# airflow_sensor_teensy2.net
KiCad netlist of a schematic drawn in EAGLE
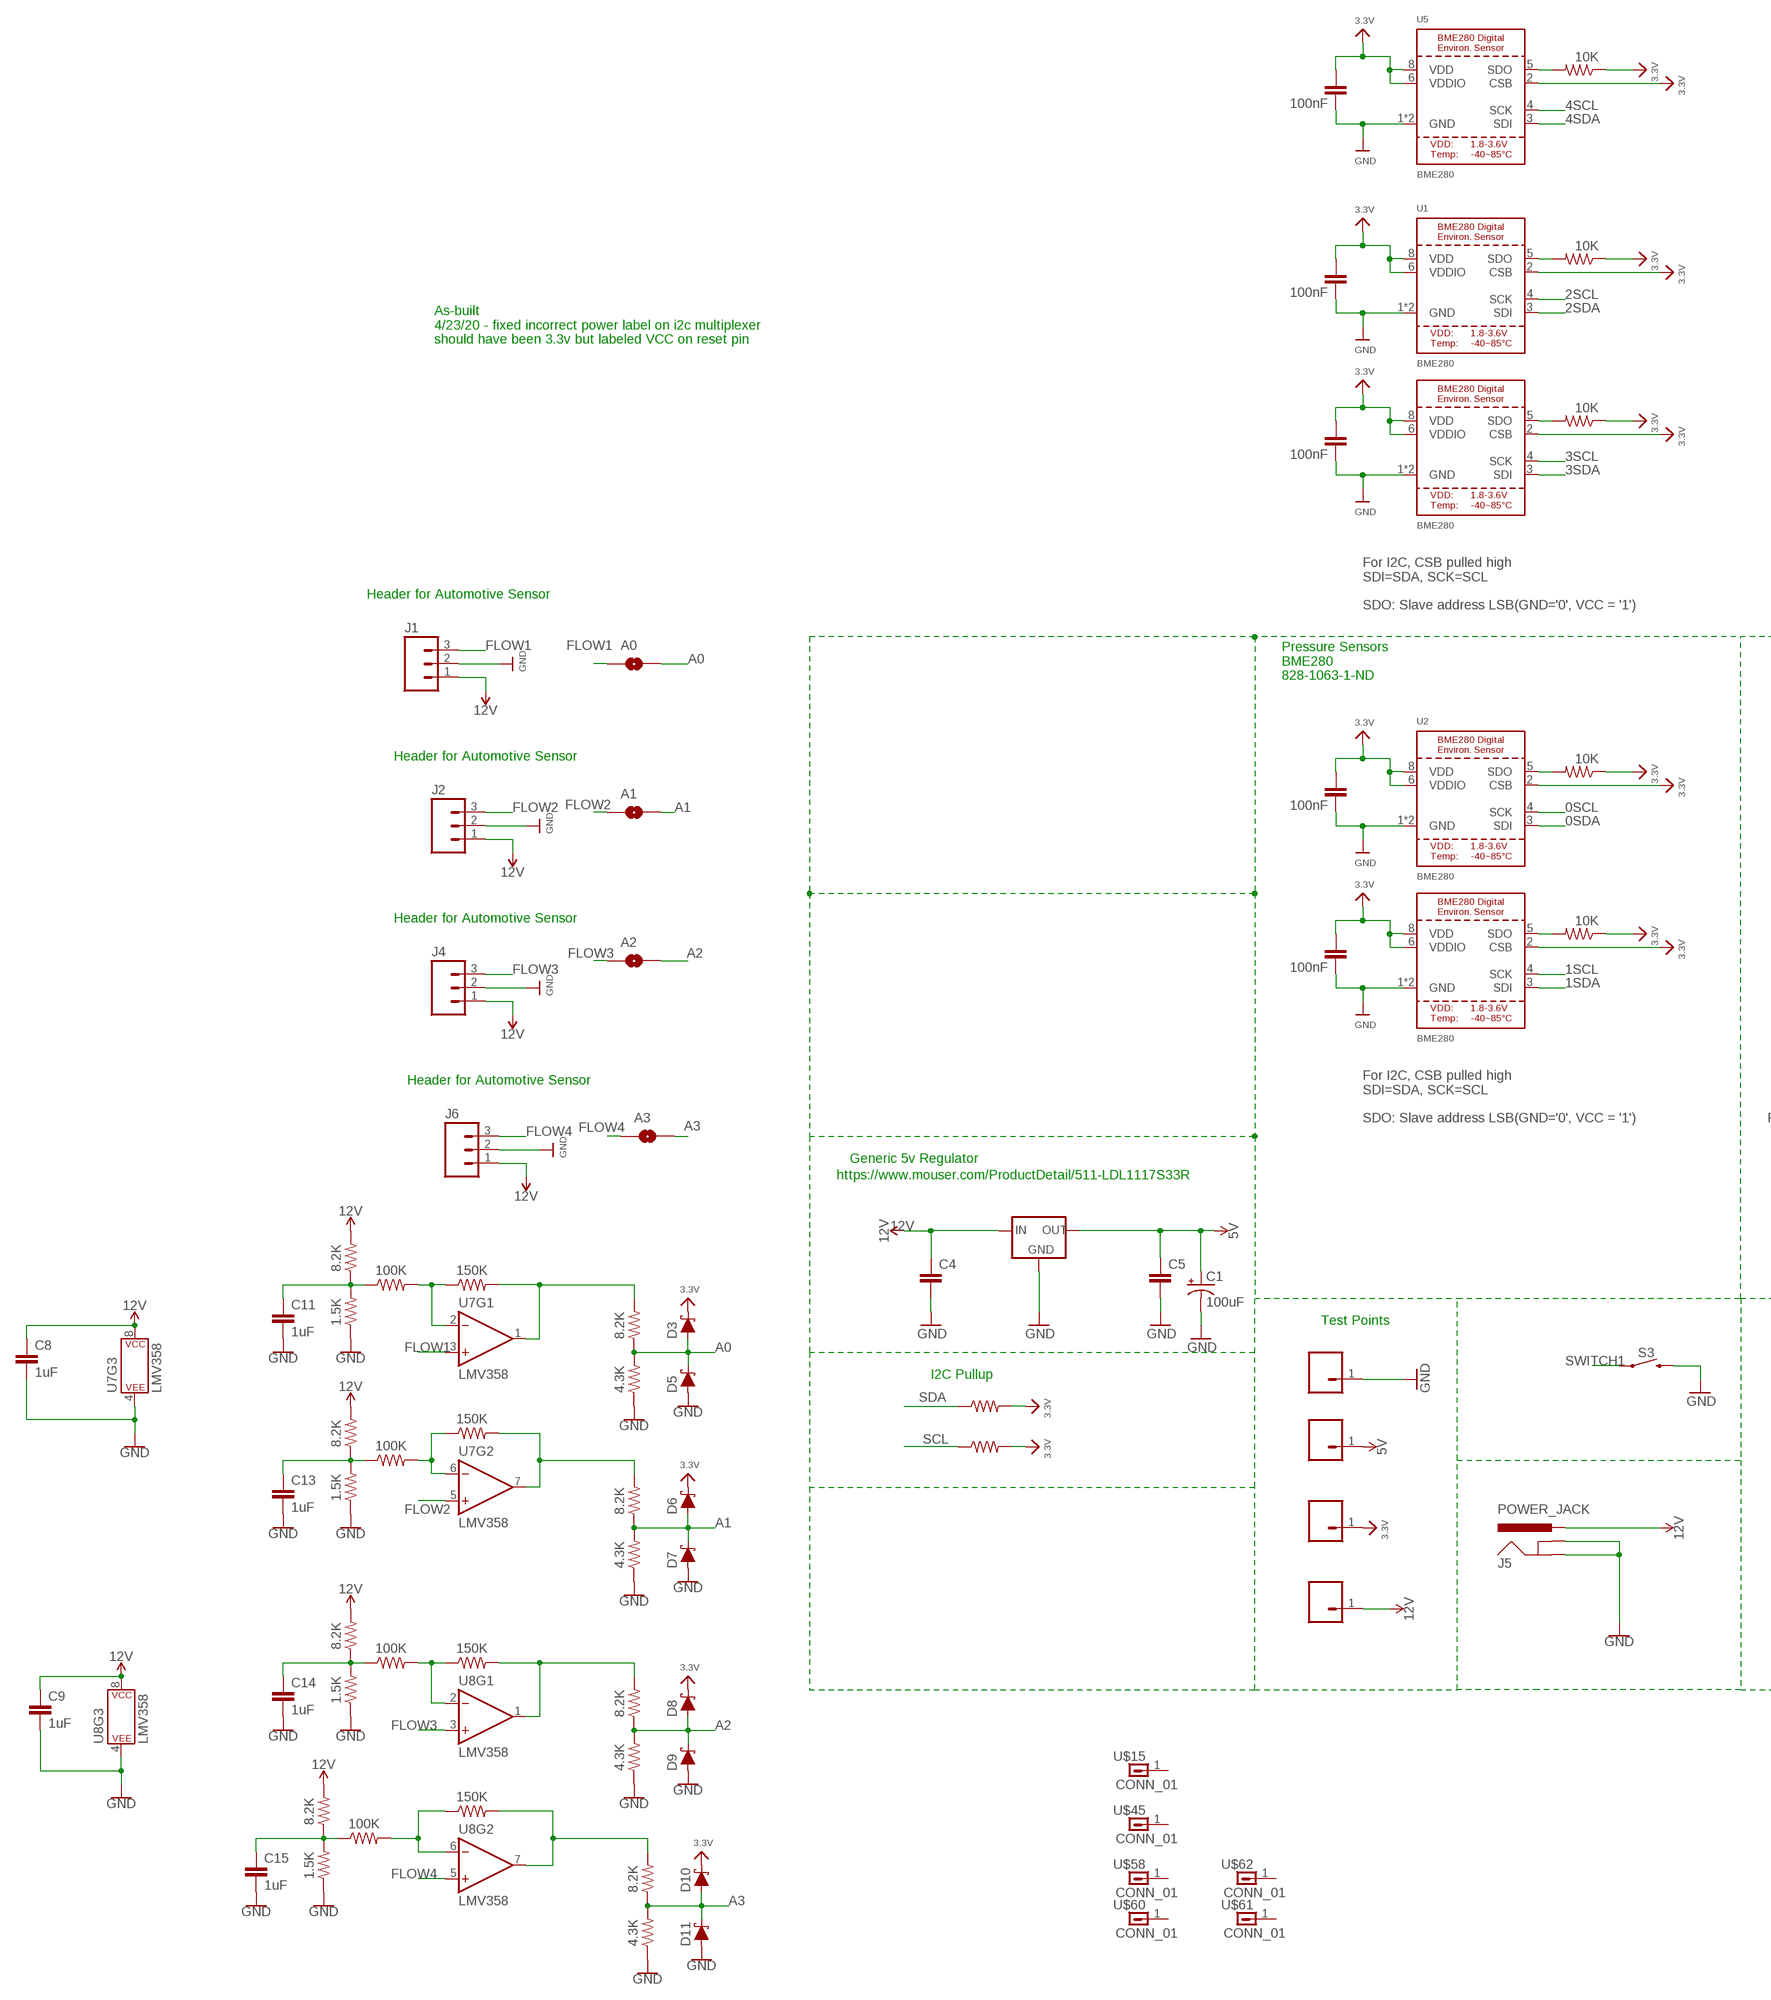
[diagram p0: schematic, sheet 1, part 1 of 2]
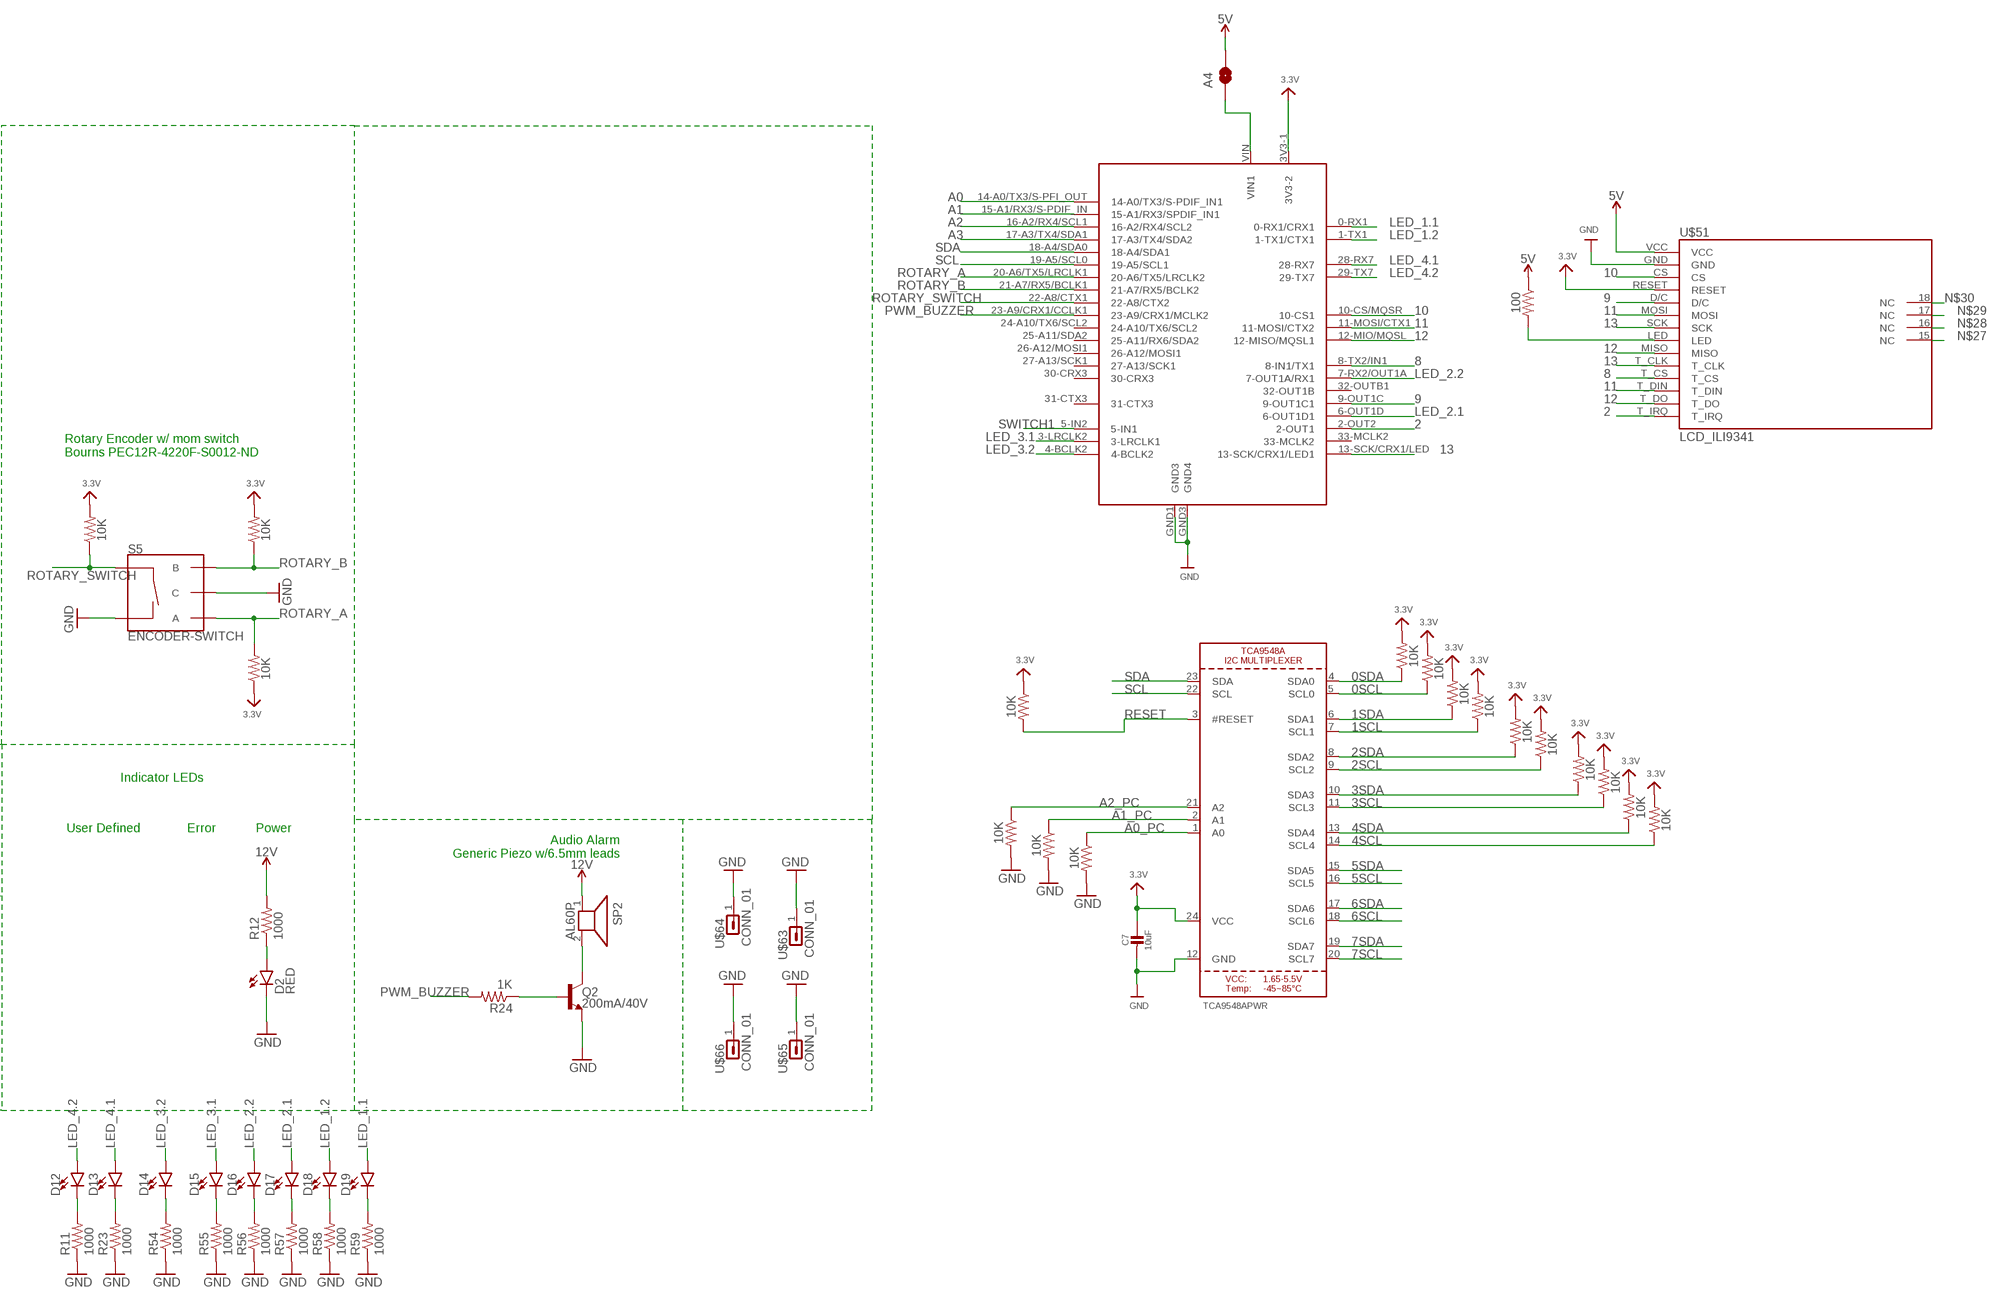
[diagram p1: schematic, sheet 1, part 2 of 2]

(export (version "E")
  (design (tool "Eeschema 10.0.6"))
  (components
    (comp (ref "3V_REGULATOR")
      (value "LDL1117_5V_REG")
      (footprint "eagle-import:SOT223")
      (libsource (lib "eagle-import") (part "LDL1117_5V_REG"))
    )
    (comp (ref "A0")
      (value "JUMPER-SMT_2_NO_NO-SILK")
      (footprint "eagle-import:SMT-JUMPER_2_NO_NO-SILK")
      (libsource (lib "eagle-import") (part "JUMPER-SMT_2_NO_NO-SILK"))
    )
    (comp (ref "A1")
      (value "JUMPER-SMT_2_NO_NO-SILK")
      (footprint "eagle-import:SMT-JUMPER_2_NO_NO-SILK")
      (libsource (lib "eagle-import") (part "JUMPER-SMT_2_NO_NO-SILK"))
    )
    (comp (ref "A2")
      (value "JUMPER-SMT_2_NO_NO-SILK")
      (footprint "eagle-import:SMT-JUMPER_2_NO_NO-SILK")
      (libsource (lib "eagle-import") (part "JUMPER-SMT_2_NO_NO-SILK"))
    )
    (comp (ref "A3")
      (value "JUMPER-SMT_2_NO_NO-SILK")
      (footprint "eagle-import:SMT-JUMPER_2_NO_NO-SILK")
      (libsource (lib "eagle-import") (part "JUMPER-SMT_2_NO_NO-SILK"))
    )
    (comp (ref "A4")
      (value "JUMPER-SMT_2_NO_NO-SILK")
      (footprint "eagle-import:SMT-JUMPER_2_NO_NO-SILK")
      (libsource (lib "eagle-import") (part "JUMPER-SMT_2_NO_NO-SILK"))
    )
    (comp (ref "C1")
      (value "100uF")
      (footprint "eagle-import:CPOL-RADIAL-2.5MM-6.5MM")
      (libsource (lib "eagle-import") (part "100UF-POLAR-RADIAL-2.5MM-25V-20%"))
    )
    (comp (ref "C2")
      (value "100nF")
      (footprint "eagle-import:0805")
      (libsource (lib "eagle-import") (part "CAP-0805"))
    )
    (comp (ref "C3")
      (value "100nF")
      (footprint "eagle-import:0805")
      (libsource (lib "eagle-import") (part "CAP-0805"))
    )
    (comp (ref "C4")
      (value "CAP-0805")
      (footprint "eagle-import:0805")
      (libsource (lib "eagle-import") (part "CAP-0805"))
    )
    (comp (ref "C5")
      (value "CAP-0805")
      (footprint "eagle-import:0805")
      (libsource (lib "eagle-import") (part "CAP-0805"))
    )
    (comp (ref "C6")
      (value "100nF")
      (footprint "eagle-import:0805")
      (libsource (lib "eagle-import") (part "CAP-0805"))
    )
    (comp (ref "C7")
      (value "10uF")
      (footprint "eagle-import:0805-NO")
      (libsource (lib "eagle-import") (part "CAP_CERAMIC0805-NOOUTLINE"))
    )
    (comp (ref "C8")
      (value "1uF")
      (footprint "eagle-import:0805")
      (libsource (lib "eagle-import") (part "CAP-0805"))
    )
    (comp (ref "C9")
      (value "1uF")
      (footprint "eagle-import:0805")
      (libsource (lib "eagle-import") (part "CAP-0805"))
    )
    (comp (ref "C10")
      (value "100nF")
      (footprint "eagle-import:0805")
      (libsource (lib "eagle-import") (part "CAP-0805"))
    )
    (comp (ref "C11")
      (value "1uF")
      (footprint "eagle-import:0805")
      (libsource (lib "eagle-import") (part "CAP-0805"))
    )
    (comp (ref "C12")
      (value "100nF")
      (footprint "eagle-import:0805")
      (libsource (lib "eagle-import") (part "CAP-0805"))
    )
    (comp (ref "C13")
      (value "1uF")
      (footprint "eagle-import:0805")
      (libsource (lib "eagle-import") (part "CAP-0805"))
    )
    (comp (ref "C14")
      (value "1uF")
      (footprint "eagle-import:0805")
      (libsource (lib "eagle-import") (part "CAP-0805"))
    )
    (comp (ref "C15")
      (value "1uF")
      (footprint "eagle-import:0805")
      (libsource (lib "eagle-import") (part "CAP-0805"))
    )
    (comp (ref "D2")
      (value "RED")
      (footprint "eagle-import:LED-1206")
      (libsource (lib "eagle-import") (part "LED-RED1206"))
    )
    (comp (ref "D3")
      (value "3A/40V/500mV")
      (footprint "eagle-import:SMA-DIODE")
      (libsource (lib "eagle-import") (part "DIODE-SCHOTTKY-B340A"))
    )
    (comp (ref "D5")
      (value "3A/40V/500mV")
      (footprint "eagle-import:SMA-DIODE")
      (libsource (lib "eagle-import") (part "DIODE-SCHOTTKY-B340A"))
    )
    (comp (ref "D6")
      (value "3A/40V/500mV")
      (footprint "eagle-import:SMA-DIODE")
      (libsource (lib "eagle-import") (part "DIODE-SCHOTTKY-B340A"))
    )
    (comp (ref "D7")
      (value "3A/40V/500mV")
      (footprint "eagle-import:SMA-DIODE")
      (libsource (lib "eagle-import") (part "DIODE-SCHOTTKY-B340A"))
    )
    (comp (ref "D8")
      (value "3A/40V/500mV")
      (footprint "eagle-import:SMA-DIODE")
      (libsource (lib "eagle-import") (part "DIODE-SCHOTTKY-B340A"))
    )
    (comp (ref "D9")
      (value "3A/40V/500mV")
      (footprint "eagle-import:SMA-DIODE")
      (libsource (lib "eagle-import") (part "DIODE-SCHOTTKY-B340A"))
    )
    (comp (ref "D10")
      (value "3A/40V/500mV")
      (footprint "eagle-import:SMA-DIODE")
      (libsource (lib "eagle-import") (part "DIODE-SCHOTTKY-B340A"))
    )
    (comp (ref "D11")
      (value "3A/40V/500mV")
      (footprint "eagle-import:SMA-DIODE")
      (libsource (lib "eagle-import") (part "DIODE-SCHOTTKY-B340A"))
    )
    (comp (ref "D12")
      (value "LED5MM")
      (footprint "eagle-import:LED_5MM")
      (libsource (lib "eagle-import") (part "LED5MM"))
    )
    (comp (ref "D13")
      (value "LED5MM")
      (footprint "eagle-import:LED_5MM")
      (libsource (lib "eagle-import") (part "LED5MM"))
    )
    (comp (ref "D14")
      (value "LED5MM")
      (footprint "eagle-import:LED_5MM")
      (libsource (lib "eagle-import") (part "LED5MM"))
    )
    (comp (ref "D15")
      (value "LED5MM")
      (footprint "eagle-import:LED_5MM")
      (libsource (lib "eagle-import") (part "LED5MM"))
    )
    (comp (ref "D16")
      (value "LED5MM")
      (footprint "eagle-import:LED_5MM")
      (libsource (lib "eagle-import") (part "LED5MM"))
    )
    (comp (ref "D17")
      (value "LED5MM")
      (footprint "eagle-import:LED_5MM")
      (libsource (lib "eagle-import") (part "LED5MM"))
    )
    (comp (ref "D18")
      (value "LED5MM")
      (footprint "eagle-import:LED_5MM")
      (libsource (lib "eagle-import") (part "LED5MM"))
    )
    (comp (ref "D19")
      (value "LED5MM")
      (footprint "eagle-import:LED_5MM")
      (libsource (lib "eagle-import") (part "LED5MM"))
    )
    (comp (ref "J1")
      (value "M03SCREW")
      (footprint "eagle-import:SCREWTERMINAL-3.5MM-3")
      (libsource (lib "eagle-import") (part "M03SCREW"))
    )
    (comp (ref "J2")
      (value "M03SCREW")
      (footprint "eagle-import:SCREWTERMINAL-3.5MM-3")
      (libsource (lib "eagle-import") (part "M03SCREW"))
    )
    (comp (ref "J4")
      (value "M03SCREW")
      (footprint "eagle-import:SCREWTERMINAL-3.5MM-3")
      (libsource (lib "eagle-import") (part "M03SCREW"))
    )
    (comp (ref "J5")
      (value "POWER_JACK")
      (footprint "eagle-import:POWER_JACK_PTH")
      (libsource (lib "eagle-import") (part "POWER_JACK"))
    )
    (comp (ref "J6")
      (value "M03SCREW")
      (footprint "eagle-import:SCREWTERMINAL-3.5MM-3")
      (libsource (lib "eagle-import") (part "M03SCREW"))
    )
    (comp (ref "Q2")
      (value "200mA/40V")
      (footprint "eagle-import:TO-92")
      (libsource (lib "eagle-import") (part "TRANS_NPN-2N3904"))
    )
    (comp (ref "R1")
      (value "10K")
      (footprint "eagle-import:0805")
      (libsource (lib "eagle-import") (part "RESISTOR0805-RES"))
    )
    (comp (ref "R2")
      (value "10K")
      (footprint "eagle-import:0805")
      (libsource (lib "eagle-import") (part "RESISTOR0805-RES"))
    )
    (comp (ref "R3")
      (value "10K")
      (footprint "eagle-import:0805")
      (libsource (lib "eagle-import") (part "RESISTOR0805-RES"))
    )
    (comp (ref "R4")
      (value "10K")
      (footprint "eagle-import:0805")
      (libsource (lib "eagle-import") (part "RESISTOR0805-RES"))
    )
    (comp (ref "R5")
      (value "10K")
      (footprint "eagle-import:0805")
      (libsource (lib "eagle-import") (part "RESISTOR0805-RES"))
    )
    (comp (ref "R6")
      (value "10K")
      (footprint "eagle-import:0805")
      (libsource (lib "eagle-import") (part "0.3OHM-0805-1/8W-1%"))
    )
    (comp (ref "R7")
      (value "10K")
      (footprint "eagle-import:0805")
      (libsource (lib "eagle-import") (part "0.3OHM-0805-1/8W-1%"))
    )
    (comp (ref "R8")
      (value "10K")
      (footprint "eagle-import:0805")
      (libsource (lib "eagle-import") (part "0.3OHM-0805-1/8W-1%"))
    )
    (comp (ref "R9")
      (value "10K")
      (footprint "eagle-import:0805")
      (libsource (lib "eagle-import") (part "0.3OHM-0805-1/8W-1%"))
    )
    (comp (ref "R10")
      (value "10K")
      (footprint "eagle-import:0805")
      (libsource (lib "eagle-import") (part "0.3OHM-0805-1/8W-1%"))
    )
    (comp (ref "R11")
      (value "1000")
      (footprint "eagle-import:0805")
      (libsource (lib "eagle-import") (part "RESISTOR0805-RES"))
    )
    (comp (ref "R12")
      (value "1000")
      (footprint "eagle-import:0805")
      (libsource (lib "eagle-import") (part "RESISTOR0805-RES"))
    )
    (comp (ref "R13")
      (value "10K")
      (footprint "eagle-import:0805")
      (libsource (lib "eagle-import") (part "0.3OHM-0805-1/8W-1%"))
    )
    (comp (ref "R14")
      (value "10K")
      (footprint "eagle-import:0805")
      (libsource (lib "eagle-import") (part "0.3OHM-0805-1/8W-1%"))
    )
    (comp (ref "R15")
      (value "10K")
      (footprint "eagle-import:0805")
      (libsource (lib "eagle-import") (part "0.3OHM-0805-1/8W-1%"))
    )
    (comp (ref "R16")
      (value "10K")
      (footprint "eagle-import:0805")
      (libsource (lib "eagle-import") (part "0.3OHM-0805-1/8W-1%"))
    )
    (comp (ref "R17")
      (value "10K")
      (footprint "eagle-import:0805")
      (libsource (lib "eagle-import") (part "0.3OHM-0805-1/8W-1%"))
    )
    (comp (ref "R18")
      (value "10K")
      (footprint "eagle-import:0805")
      (libsource (lib "eagle-import") (part "0.3OHM-0805-1/8W-1%"))
    )
    (comp (ref "R19")
      (value "10K")
      (footprint "eagle-import:0805")
      (libsource (lib "eagle-import") (part "0.3OHM-0805-1/8W-1%"))
    )
    (comp (ref "R20")
      (value "10K")
      (footprint "eagle-import:0805")
      (libsource (lib "eagle-import") (part "0.3OHM-0805-1/8W-1%"))
    )
    (comp (ref "R21")
      (value "0.3")
      (footprint "eagle-import:0805")
      (libsource (lib "eagle-import") (part "0.3OHM-0805-1/8W-1%"))
    )
    (comp (ref "R22")
      (value "0.3")
      (footprint "eagle-import:0805")
      (libsource (lib "eagle-import") (part "0.3OHM-0805-1/8W-1%"))
    )
    (comp (ref "R23")
      (value "1000")
      (footprint "eagle-import:0805")
      (libsource (lib "eagle-import") (part "RESISTOR0805-RES"))
    )
    (comp (ref "R24")
      (value "1K")
      (footprint "eagle-import:0805")
      (libsource (lib "eagle-import") (part "RESISTOR0805-RES"))
    )
    (comp (ref "R25")
      (value "10K")
      (footprint "eagle-import:0805")
      (libsource (lib "eagle-import") (part "0.3OHM-0805-1/8W-1%"))
    )
    (comp (ref "R26")
      (value "10K")
      (footprint "eagle-import:0805")
      (libsource (lib "eagle-import") (part "0.3OHM-0805-1/8W-1%"))
    )
    (comp (ref "R27")
      (value "10K")
      (footprint "eagle-import:0805")
      (libsource (lib "eagle-import") (part "0.3OHM-0805-1/8W-1%"))
    )
    (comp (ref "R28")
      (value "10K")
      (footprint "eagle-import:0805")
      (libsource (lib "eagle-import") (part "0.3OHM-0805-1/8W-1%"))
    )
    (comp (ref "R29")
      (value "150K")
      (footprint "eagle-import:0805")
      (libsource (lib "eagle-import") (part "0.3OHM-0805-1/8W-1%"))
    )
    (comp (ref "R30")
      (value "150K")
      (footprint "eagle-import:0805")
      (libsource (lib "eagle-import") (part "0.3OHM-0805-1/8W-1%"))
    )
    (comp (ref "R31")
      (value "150K")
      (footprint "eagle-import:0805")
      (libsource (lib "eagle-import") (part "0.3OHM-0805-1/8W-1%"))
    )
    (comp (ref "R32")
      (value "150K")
      (footprint "eagle-import:0805")
      (libsource (lib "eagle-import") (part "0.3OHM-0805-1/8W-1%"))
    )
    (comp (ref "R33")
      (value "4.3K")
      (footprint "eagle-import:0805")
      (libsource (lib "eagle-import") (part "0.3OHM-0805-1/8W-1%"))
    )
    (comp (ref "R34")
      (value "8.2K")
      (footprint "eagle-import:0805")
      (libsource (lib "eagle-import") (part "0.3OHM-0805-1/8W-1%"))
    )
    (comp (ref "R35")
      (value "4.3K")
      (footprint "eagle-import:0805")
      (libsource (lib "eagle-import") (part "0.3OHM-0805-1/8W-1%"))
    )
    (comp (ref "R36")
      (value "8.2K")
      (footprint "eagle-import:0805")
      (libsource (lib "eagle-import") (part "0.3OHM-0805-1/8W-1%"))
    )
    (comp (ref "R37")
      (value "4.3K")
      (footprint "eagle-import:0805")
      (libsource (lib "eagle-import") (part "0.3OHM-0805-1/8W-1%"))
    )
    (comp (ref "R38")
      (value "8.2K")
      (footprint "eagle-import:0805")
      (libsource (lib "eagle-import") (part "0.3OHM-0805-1/8W-1%"))
    )
    (comp (ref "R39")
      (value "4.3K")
      (footprint "eagle-import:0805")
      (libsource (lib "eagle-import") (part "0.3OHM-0805-1/8W-1%"))
    )
    (comp (ref "R40")
      (value "8.2K")
      (footprint "eagle-import:0805")
      (libsource (lib "eagle-import") (part "0.3OHM-0805-1/8W-1%"))
    )
    (comp (ref "R41")
      (value "8.2K")
      (footprint "eagle-import:0805")
      (libsource (lib "eagle-import") (part "0.3OHM-0805-1/8W-1%"))
    )
    (comp (ref "R42")
      (value "1.5K")
      (footprint "eagle-import:0805")
      (libsource (lib "eagle-import") (part "0.3OHM-0805-1/8W-1%"))
    )
    (comp (ref "R43")
      (value "100K")
      (footprint "eagle-import:0805")
      (libsource (lib "eagle-import") (part "0.3OHM-0805-1/8W-1%"))
    )
    (comp (ref "R44")
      (value "8.2K")
      (footprint "eagle-import:0805")
      (libsource (lib "eagle-import") (part "0.3OHM-0805-1/8W-1%"))
    )
    (comp (ref "R45")
      (value "1.5K")
      (footprint "eagle-import:0805")
      (libsource (lib "eagle-import") (part "0.3OHM-0805-1/8W-1%"))
    )
    (comp (ref "R46")
      (value "100K")
      (footprint "eagle-import:0805")
      (libsource (lib "eagle-import") (part "0.3OHM-0805-1/8W-1%"))
    )
    (comp (ref "R47")
      (value "8.2K")
      (footprint "eagle-import:0805")
      (libsource (lib "eagle-import") (part "0.3OHM-0805-1/8W-1%"))
    )
    (comp (ref "R48")
      (value "1.5K")
      (footprint "eagle-import:0805")
      (libsource (lib "eagle-import") (part "0.3OHM-0805-1/8W-1%"))
    )
    (comp (ref "R49")
      (value "100K")
      (footprint "eagle-import:0805")
      (libsource (lib "eagle-import") (part "0.3OHM-0805-1/8W-1%"))
    )
    (comp (ref "R50")
      (value "8.2K")
      (footprint "eagle-import:0805")
      (libsource (lib "eagle-import") (part "0.3OHM-0805-1/8W-1%"))
    )
    (comp (ref "R51")
      (value "1.5K")
      (footprint "eagle-import:0805")
      (libsource (lib "eagle-import") (part "0.3OHM-0805-1/8W-1%"))
    )
    (comp (ref "R52")
      (value "100K")
      (footprint "eagle-import:0805")
      (libsource (lib "eagle-import") (part "0.3OHM-0805-1/8W-1%"))
    )
    (comp (ref "R53")
      (value "100")
      (footprint "eagle-import:0805")
      (libsource (lib "eagle-import") (part "0.3OHM-0805-1/8W-1%"))
    )
    (comp (ref "R54")
      (value "1000")
      (footprint "eagle-import:0805")
      (libsource (lib "eagle-import") (part "RESISTOR0805-RES"))
    )
    (comp (ref "R55")
      (value "1000")
      (footprint "eagle-import:0805")
      (libsource (lib "eagle-import") (part "RESISTOR0805-RES"))
    )
    (comp (ref "R56")
      (value "1000")
      (footprint "eagle-import:0805")
      (libsource (lib "eagle-import") (part "RESISTOR0805-RES"))
    )
    (comp (ref "R57")
      (value "1000")
      (footprint "eagle-import:0805")
      (libsource (lib "eagle-import") (part "RESISTOR0805-RES"))
    )
    (comp (ref "R58")
      (value "1000")
      (footprint "eagle-import:0805")
      (libsource (lib "eagle-import") (part "RESISTOR0805-RES"))
    )
    (comp (ref "R59")
      (value "1000")
      (footprint "eagle-import:0805")
      (libsource (lib "eagle-import") (part "RESISTOR0805-RES"))
    )
    (comp (ref "S3")
      (value "MOMENTARY-SWITCH-SPST-PTH-6.0MM-KIT")
      (footprint "eagle-import:TACTILE_SWITCH_PTH_6.0MM_KIT")
      (libsource (lib "eagle-import") (part "MOMENTARY-SWITCH-SPST-PTH-6.0MM-KIT"))
    )
    (comp (ref "S5")
      (value "ENCODER-SWITCH")
      (footprint "eagle-import:ROTARY_ENC_PLAIN")
      (libsource (lib "eagle-import") (part "ENCODER-SWITCH"))
    )
    (comp (ref "SP2")
      (value "AL60P")
      (footprint "eagle-import:AL60P")
      (libsource (lib "eagle-import") (part "AL60P"))
    )
    (comp (ref "U$15")
      (value "CONN_01")
      (footprint "eagle-import:1X01-#6_MACHINE")
      (libsource (lib "eagle-import") (part "CONN_01"))
    )
    (comp (ref "U$20")
      (value "CONN_0138MILL")
      (footprint "eagle-import:1X01-40MILL")
      (libsource (lib "eagle-import") (part "th_libraries3_CONN_0138MILL"))
    )
    (comp (ref "U$31")
      (value "CONN_0138MILL")
      (footprint "eagle-import:1X01-40MILL")
      (libsource (lib "eagle-import") (part "th_libraries3_CONN_0138MILL"))
    )
    (comp (ref "U$40")
      (value "CONN_0138MILL")
      (footprint "eagle-import:1X01-40MILL")
      (libsource (lib "eagle-import") (part "th_libraries3_CONN_0138MILL"))
    )
    (comp (ref "U$45")
      (value "CONN_01")
      (footprint "eagle-import:1X01-#6_MACHINE")
      (libsource (lib "eagle-import") (part "CONN_01"))
    )
    (comp (ref "U$51")
      (value "LCD_ILI9341")
      (footprint "eagle-import:ILI9341")
      (libsource (lib "eagle-import") (part "LCD_ILI9341"))
    )
    (comp (ref "U$58")
      (value "CONN_01")
      (footprint "eagle-import:1X01-#6_MACHINE")
      (libsource (lib "eagle-import") (part "CONN_01"))
    )
    (comp (ref "U$59")
      (value "CONN_0138MILL")
      (footprint "eagle-import:1X01-40MILL")
      (libsource (lib "eagle-import") (part "th_libraries3_CONN_0138MILL"))
    )
    (comp (ref "U$60")
      (value "CONN_01")
      (footprint "eagle-import:1X01-#6_MACHINE")
      (libsource (lib "eagle-import") (part "CONN_01"))
    )
    (comp (ref "U$61")
      (value "CONN_01")
      (footprint "eagle-import:1X01-#6_MACHINE")
      (libsource (lib "eagle-import") (part "CONN_01"))
    )
    (comp (ref "U$62")
      (value "CONN_01")
      (footprint "eagle-import:1X01-#6_MACHINE")
      (libsource (lib "eagle-import") (part "CONN_01"))
    )
    (comp (ref "U$63")
      (value "CONN_01")
      (footprint "eagle-import:1X01-#6_MACHINE")
      (libsource (lib "eagle-import") (part "CONN_01"))
    )
    (comp (ref "U$64")
      (value "CONN_01")
      (footprint "eagle-import:1X01-#6_MACHINE")
      (libsource (lib "eagle-import") (part "CONN_01"))
    )
    (comp (ref "U$65")
      (value "CONN_01")
      (footprint "eagle-import:1X01-#6_MACHINE")
      (libsource (lib "eagle-import") (part "CONN_01"))
    )
    (comp (ref "U$66")
      (value "CONN_01")
      (footprint "eagle-import:1X01-#6_MACHINE")
      (libsource (lib "eagle-import") (part "CONN_01"))
    )
    (comp (ref "U$67")
      (value "TEENSY_ALL_PINS")
      (footprint "eagle-import:TEENSY4-ALL_PINS")
      (libsource (lib "eagle-import") (part "TEENSY_ALL_PINS"))
    )
    (comp (ref "U1")
      (value "BME280")
      (footprint "eagle-import:BME280")
      (libsource (lib "eagle-import") (part "BME280"))
    )
    (comp (ref "U2")
      (value "BME280")
      (footprint "eagle-import:BME280")
      (libsource (lib "eagle-import") (part "BME280"))
    )
    (comp (ref "U3")
      (value "BME280")
      (footprint "eagle-import:BME280")
      (libsource (lib "eagle-import") (part "BME280"))
    )
    (comp (ref "U4")
      (value "BME280")
      (footprint "eagle-import:BME280")
      (libsource (lib "eagle-import") (part "BME280"))
    )
    (comp (ref "U5")
      (value "BME280")
      (footprint "eagle-import:BME280")
      (libsource (lib "eagle-import") (part "BME280"))
    )
    (comp (ref "U6")
      (value "TCA9548APWR")
      (footprint "eagle-import:TSSOP24")
      (libsource (lib "eagle-import") (part "TCA9548A"))
    )
    (comp (ref "U7")
      (value "LMV358")
      (footprint "eagle-import:SO08")
      (libsource (lib "eagle-import") (part "LMV358SOIC"))
    )
    (comp (ref "U8")
      (value "LMV358")
      (footprint "eagle-import:SO08")
      (libsource (lib "eagle-import") (part "LMV358SOIC"))
    )
  )
  (nets
    (net (code "1") (name "/0SCL") (class "Default")
      (node (ref "R8") (pin "1") (pinfunction "1_1") (pintype "passive"))
      (node (ref "U2") (pin "4") (pinfunction "SCK_4") (pintype "input"))
      (node (ref "U6") (pin "5") (pinfunction "SCL0_5") (pintype "bidirectional"))
    )
    (net (code "2") (name "/0SDA") (class "Default")
      (node (ref "R7") (pin "1") (pinfunction "1_1") (pintype "passive"))
      (node (ref "U2") (pin "3") (pinfunction "SDI_3") (pintype "input"))
      (node (ref "U6") (pin "4") (pinfunction "SDA0_4") (pintype "bidirectional"))
    )
    (net (code "3") (name "/1SCL") (class "Default")
      (node (ref "R10") (pin "1") (pinfunction "1_1") (pintype "passive"))
      (node (ref "U4") (pin "4") (pinfunction "SCK_4") (pintype "input"))
      (node (ref "U6") (pin "7") (pinfunction "SCL1_7") (pintype "bidirectional"))
    )
    (net (code "4") (name "/1SDA") (class "Default")
      (node (ref "R9") (pin "1") (pinfunction "1_1") (pintype "passive"))
      (node (ref "U4") (pin "3") (pinfunction "SDI_3") (pintype "input"))
      (node (ref "U6") (pin "6") (pinfunction "SDA1_6") (pintype "bidirectional"))
    )
    (net (code "5") (name "/2") (class "Default")
      (node (ref "U$51") (pin "T_IRQ") (pinfunction "T_IRQ_T_IRQ") (pintype "input"))
      (node (ref "U$67") (pin "2-OUT2") (pinfunction "2-OUT1_2-OUT2") (pintype "bidirectional"))
    )
    (net (code "6") (name "/2SCL") (class "Default")
      (node (ref "R14") (pin "1") (pinfunction "1_1") (pintype "passive"))
      (node (ref "U1") (pin "4") (pinfunction "SCK_4") (pintype "input"))
      (node (ref "U6") (pin "9") (pinfunction "SCL2_9") (pintype "bidirectional"))
    )
    (net (code "7") (name "/2SDA") (class "Default")
      (node (ref "R13") (pin "1") (pinfunction "1_1") (pintype "passive"))
      (node (ref "U1") (pin "3") (pinfunction "SDI_3") (pintype "input"))
      (node (ref "U6") (pin "8") (pinfunction "SDA2_8") (pintype "bidirectional"))
    )
    (net (code "8") (name "/3SCL") (class "Default")
      (node (ref "R16") (pin "1") (pinfunction "1_1") (pintype "passive"))
      (node (ref "U3") (pin "4") (pinfunction "SCK_4") (pintype "input"))
      (node (ref "U6") (pin "11") (pinfunction "SCL3_11") (pintype "bidirectional"))
    )
    (net (code "9") (name "/3SDA") (class "Default")
      (node (ref "R15") (pin "1") (pinfunction "1_1") (pintype "passive"))
      (node (ref "U3") (pin "3") (pinfunction "SDI_3") (pintype "input"))
      (node (ref "U6") (pin "10") (pinfunction "SDA3_10") (pintype "bidirectional"))
    )
    (net (code "10") (name "/4SCL") (class "Default")
      (node (ref "R18") (pin "1") (pinfunction "1_1") (pintype "passive"))
      (node (ref "U5") (pin "4") (pinfunction "SCK_4") (pintype "input"))
      (node (ref "U6") (pin "14") (pinfunction "SCL4_14") (pintype "bidirectional"))
    )
    (net (code "11") (name "/4SDA") (class "Default")
      (node (ref "R17") (pin "1") (pinfunction "1_1") (pintype "passive"))
      (node (ref "U5") (pin "3") (pinfunction "SDI_3") (pintype "input"))
      (node (ref "U6") (pin "13") (pinfunction "SDA4_13") (pintype "bidirectional"))
    )
    (net (code "12") (name "/5SCL") (class "Default")
      (node (ref "U6") (pin "16") (pinfunction "SCL5_16") (pintype "bidirectional"))
    )
    (net (code "13") (name "/5SDA") (class "Default")
      (node (ref "U6") (pin "15") (pinfunction "SDA5_15") (pintype "bidirectional"))
    )
    (net (code "14") (name "/6SCL") (class "Default")
      (node (ref "U6") (pin "18") (pinfunction "SCL6_18") (pintype "bidirectional"))
    )
    (net (code "15") (name "/6SDA") (class "Default")
      (node (ref "U6") (pin "17") (pinfunction "SDA6_17") (pintype "bidirectional"))
    )
    (net (code "16") (name "/7SCL") (class "Default")
      (node (ref "U6") (pin "20") (pinfunction "SCL7_20") (pintype "bidirectional"))
    )
    (net (code "17") (name "/7SDA") (class "Default")
      (node (ref "U6") (pin "19") (pinfunction "SDA7_19") (pintype "bidirectional"))
    )
    (net (code "18") (name "/8") (class "Default")
      (node (ref "U$51") (pin "T_CS") (pinfunction "T_CS_T_CS") (pintype "bidirectional"))
      (node (ref "U$67") (pin "8-TX2/IN1") (pinfunction "8-IN1/TX1_8-TX2/IN1") (pintype "bidirectional"))
    )
    (net (code "19") (name "/9") (class "Default")
      (node (ref "U$51") (pin "D/C") (pinfunction "D/C_D/C") (pintype "bidirectional"))
      (node (ref "U$67") (pin "9-OUT1C") (pinfunction "9-OUT1C1_9-OUT1C") (pintype "bidirectional"))
    )
    (net (code "20") (name "/10") (class "Default")
      (node (ref "U$51") (pin "CS") (pinfunction "CS_CS") (pintype "bidirectional"))
      (node (ref "U$67") (pin "10-CS/MQSR") (pinfunction "10-CS1_10-CS/MQSR") (pintype "bidirectional"))
    )
    (net (code "21") (name "/11") (class "Default")
      (node (ref "U$51") (pin "MOSI") (pinfunction "MOSI_MOSI") (pintype "bidirectional"))
      (node (ref "U$51") (pin "T_DIN") (pinfunction "T_DIN_T_DIN") (pintype "input"))
      (node (ref "U$67") (pin "11-MOSI/CTX1") (pinfunction "11-MOSI/CTX2_11-MOSI/CTX1") (pintype "bidirectional"))
    )
    (net (code "22") (name "/12") (class "Default")
      (node (ref "U$51") (pin "MISO") (pinfunction "MISO_MISO") (pintype "bidirectional"))
      (node (ref "U$51") (pin "T_DO") (pinfunction "T_DO_T_DO") (pintype "input"))
      (node (ref "U$67") (pin "12-MIO/MQSL") (pinfunction "12-MISO/MQSL1_12-MIO/MQSL") (pintype "bidirectional"))
    )
    (net (code "23") (name "/13") (class "Default")
      (node (ref "U$51") (pin "SCK") (pinfunction "SCK_SCK") (pintype "bidirectional"))
      (node (ref "U$51") (pin "T_CLK") (pinfunction "T_CLK_T_CLK") (pintype "bidirectional"))
      (node (ref "U$67") (pin "13-SCK/CRX1/LED") (pinfunction "13-SCK/CRX1/LED1_13-SCK/CRX1/LED") (pintype "bidirectional"))
    )
    (net (code "24") (name "/A0") (class "Default")
      (node (ref "A0") (pin "2") (pinfunction "2_2") (pintype "passive"))
      (node (ref "D3") (pin "A") (pinfunction "A_A") (pintype "passive"))
      (node (ref "D5") (pin "C") (pinfunction "C_C") (pintype "passive"))
      (node (ref "R33") (pin "2") (pinfunction "2_2") (pintype "passive"))
      (node (ref "R40") (pin "1") (pinfunction "1_1") (pintype "passive"))
      (node (ref "U$67") (pin "14-A0/TX3/S-PFI_OUT") (pinfunction "14-A0/TX3/S-PDIF_IN1_14-A0/TX3/S-PFI_OUT") (pintype "bidirectional"))
    )
    (net (code "25") (name "/A0_PC") (class "Default")
      (node (ref "R19") (pin "1") (pinfunction "1_1") (pintype "passive"))
      (node (ref "U6") (pin "1") (pinfunction "A0_1") (pintype "bidirectional"))
    )
    (net (code "26") (name "/A1") (class "Default")
      (node (ref "A1") (pin "2") (pinfunction "2_2") (pintype "passive"))
      (node (ref "D6") (pin "A") (pinfunction "A_A") (pintype "passive"))
      (node (ref "D7") (pin "C") (pinfunction "C_C") (pintype "passive"))
      (node (ref "R34") (pin "1") (pinfunction "1_1") (pintype "passive"))
      (node (ref "R35") (pin "2") (pinfunction "2_2") (pintype "passive"))
      (node (ref "U$67") (pin "15-A1/RX3/S-PDIF_IN") (pinfunction "15-A1/RX3/SPDIF_IN1_15-A1/RX3/S-PDIF_IN") (pintype "bidirectional"))
    )
    (net (code "27") (name "/A1_PC") (class "Default")
      (node (ref "R20") (pin "1") (pinfunction "1_1") (pintype "passive"))
      (node (ref "U6") (pin "2") (pinfunction "A1_2") (pintype "bidirectional"))
    )
    (net (code "28") (name "/A2") (class "Default")
      (node (ref "A2") (pin "2") (pinfunction "2_2") (pintype "passive"))
      (node (ref "D8") (pin "A") (pinfunction "A_A") (pintype "passive"))
      (node (ref "D9") (pin "C") (pinfunction "C_C") (pintype "passive"))
      (node (ref "R36") (pin "1") (pinfunction "1_1") (pintype "passive"))
      (node (ref "R37") (pin "2") (pinfunction "2_2") (pintype "passive"))
      (node (ref "U$67") (pin "16-A2/RX4/SCL1") (pinfunction "16-A2/RX4/SCL2_16-A2/RX4/SCL1") (pintype "bidirectional"))
    )
    (net (code "29") (name "/A2_PC") (class "Default")
      (node (ref "R25") (pin "1") (pinfunction "1_1") (pintype "passive"))
      (node (ref "U6") (pin "21") (pinfunction "A2_21") (pintype "bidirectional"))
    )
    (net (code "30") (name "/A3") (class "Default")
      (node (ref "A3") (pin "2") (pinfunction "2_2") (pintype "passive"))
      (node (ref "D10") (pin "A") (pinfunction "A_A") (pintype "passive"))
      (node (ref "D11") (pin "C") (pinfunction "C_C") (pintype "passive"))
      (node (ref "R38") (pin "1") (pinfunction "1_1") (pintype "passive"))
      (node (ref "R39") (pin "2") (pinfunction "2_2") (pintype "passive"))
      (node (ref "U$67") (pin "17-A3/TX4/SDA1") (pinfunction "17-A3/TX4/SDA2_17-A3/TX4/SDA1") (pintype "bidirectional"))
    )
    (net (code "31") (name "/FLOW1") (class "Default")
      (node (ref "A0") (pin "1") (pinfunction "1_1") (pintype "passive"))
      (node (ref "J1") (pin "3") (pinfunction "3_3") (pintype "passive"))
      (node (ref "U7") (pin "3") (pinfunction "+IN_3") (pintype "input"))
    )
    (net (code "32") (name "/FLOW2") (class "Default")
      (node (ref "A1") (pin "1") (pinfunction "1_1") (pintype "passive"))
      (node (ref "J2") (pin "3") (pinfunction "3_3") (pintype "passive"))
      (node (ref "U7") (pin "5") (pinfunction "+IN_5") (pintype "input"))
    )
    (net (code "33") (name "/FLOW3") (class "Default")
      (node (ref "A2") (pin "1") (pinfunction "1_1") (pintype "passive"))
      (node (ref "J4") (pin "3") (pinfunction "3_3") (pintype "passive"))
      (node (ref "U8") (pin "3") (pinfunction "+IN_3") (pintype "input"))
    )
    (net (code "34") (name "/FLOW4") (class "Default")
      (node (ref "A3") (pin "1") (pinfunction "1_1") (pintype "passive"))
      (node (ref "J6") (pin "3") (pinfunction "3_3") (pintype "passive"))
      (node (ref "U8") (pin "5") (pinfunction "+IN_5") (pintype "input"))
    )
    (net (code "35") (name "/LED_1.1") (class "Default")
      (node (ref "D19") (pin "A") (pinfunction "A_A") (pintype "passive"))
      (node (ref "U$67") (pin "0-RX1") (pinfunction "0-RX1/CRX1_0-RX1") (pintype "bidirectional"))
    )
    (net (code "36") (name "/LED_1.2") (class "Default")
      (node (ref "D18") (pin "A") (pinfunction "A_A") (pintype "passive"))
      (node (ref "U$67") (pin "1-TX1") (pinfunction "1-TX1/CTX1_1-TX1") (pintype "bidirectional"))
    )
    (net (code "37") (name "/LED_2.1") (class "Default")
      (node (ref "D17") (pin "A") (pinfunction "A_A") (pintype "passive"))
      (node (ref "U$67") (pin "6-OUT1D") (pinfunction "6-OUT1D1_6-OUT1D") (pintype "bidirectional"))
    )
    (net (code "38") (name "/LED_2.2") (class "Default")
      (node (ref "D16") (pin "A") (pinfunction "A_A") (pintype "passive"))
      (node (ref "U$67") (pin "7-RX2/OUT1A") (pinfunction "7-OUT1A/RX1_7-RX2/OUT1A") (pintype "bidirectional"))
    )
    (net (code "39") (name "/LED_3.1") (class "Default")
      (node (ref "D15") (pin "A") (pinfunction "A_A") (pintype "passive"))
      (node (ref "U$67") (pin "3-LRCLK2") (pinfunction "3-LRCLK1_3-LRCLK2") (pintype "bidirectional"))
    )
    (net (code "40") (name "/LED_3.2") (class "Default")
      (node (ref "D14") (pin "A") (pinfunction "A_A") (pintype "passive"))
      (node (ref "U$67") (pin "4-BCLK2") (pinfunction "4-BCLK2_4-BCLK2") (pintype "bidirectional"))
    )
    (net (code "41") (name "/LED_4.1") (class "Default")
      (node (ref "D13") (pin "A") (pinfunction "A_A") (pintype "passive"))
      (node (ref "U$67") (pin "28-RX7") (pinfunction "28-RX7_28-RX7") (pintype "bidirectional"))
    )
    (net (code "42") (name "/LED_4.2") (class "Default")
      (node (ref "D12") (pin "A") (pinfunction "A_A") (pintype "passive"))
      (node (ref "U$67") (pin "29-TX7") (pinfunction "29-TX7_29-TX7") (pintype "bidirectional"))
    )
    (net (code "43") (name "/N$27") (class "Default")
      (node (ref "U$51") (pin "15") (pinfunction "NC_15") (pintype "power_in"))
    )
    (net (code "44") (name "/N$28") (class "Default")
      (node (ref "U$51") (pin "16") (pinfunction "NC_16") (pintype "power_in"))
    )
    (net (code "45") (name "/N$29") (class "Default")
      (node (ref "U$51") (pin "17") (pinfunction "NC_17") (pintype "power_in"))
    )
    (net (code "46") (name "/N$30") (class "Default")
      (node (ref "U$51") (pin "18") (pinfunction "NC_18") (pintype "power_in"))
    )
    (net (code "47") (name "/PWM_BUZZER") (class "Default")
      (node (ref "R24") (pin "2") (pinfunction "2_2") (pintype "passive"))
      (node (ref "U$67") (pin "23-A9/CRX1/CCLK1") (pinfunction "23-A9/CRX1/MCLK2_23-A9/CRX1/CCLK1") (pintype "bidirectional"))
    )
    (net (code "48") (name "/RESET") (class "Default")
      (node (ref "R6") (pin "2") (pinfunction "2_2") (pintype "passive"))
      (node (ref "U6") (pin "3") (pinfunction "#RESET_3") (pintype "bidirectional"))
    )
    (net (code "49") (name "/ROTARY_A") (class "Default")
      (node (ref "R27") (pin "2") (pinfunction "2_2") (pintype "passive"))
      (node (ref "S5") (pin "A") (pinfunction "A_A") (pintype "bidirectional"))
      (node (ref "U$67") (pin "20-A6/TX5/LRCLK1") (pinfunction "20-A6/TX5/LRCLK2_20-A6/TX5/LRCLK1") (pintype "bidirectional"))
    )
    (net (code "50") (name "/ROTARY_B") (class "Default")
      (node (ref "R26") (pin "1") (pinfunction "1_1") (pintype "passive"))
      (node (ref "S5") (pin "B") (pinfunction "B_B") (pintype "bidirectional"))
      (node (ref "U$67") (pin "21-A7/RX5/BCLK1") (pinfunction "21-A7/RX5/BCLK2_21-A7/RX5/BCLK1") (pintype "bidirectional"))
    )
    (net (code "51") (name "/ROTARY_SWITCH") (class "Default")
      (node (ref "R28") (pin "1") (pinfunction "1_1") (pintype "passive"))
      (node (ref "S5") (pin "SW+") (pinfunction "SW+_SW+") (pintype "bidirectional"))
      (node (ref "U$67") (pin "22-A8/CTX1") (pinfunction "22-A8/CTX2_22-A8/CTX1") (pintype "bidirectional"))
    )
    (net (code "52") (name "/SCL") (class "Default")
      (node (ref "R22") (pin "1") (pinfunction "1_1") (pintype "passive"))
      (node (ref "U$67") (pin "19-A5/SCL0") (pinfunction "19-A5/SCL1_19-A5/SCL0") (pintype "bidirectional"))
      (node (ref "U6") (pin "22") (pinfunction "SCL_22") (pintype "bidirectional"))
    )
    (net (code "53") (name "/SDA") (class "Default")
      (node (ref "R21") (pin "1") (pinfunction "1_1") (pintype "passive"))
      (node (ref "U$67") (pin "18-A4/SDA0") (pinfunction "18-A4/SDA1_18-A4/SDA0") (pintype "bidirectional"))
      (node (ref "U6") (pin "23") (pinfunction "SDA_23") (pintype "bidirectional"))
    )
    (net (code "54") (name "/SWITCH1") (class "Default")
      (node (ref "S3") (pin "1") (pinfunction "1_1") (pintype "passive"))
      (node (ref "U$67") (pin "5-IN2") (pinfunction "5-IN1_5-IN2") (pintype "bidirectional"))
    )
    (net (code "55") (name "3.3V") (class "Default")
      (node (ref "C10") (pin "1") (pinfunction "1_1") (pintype "passive"))
      (node (ref "C12") (pin "1") (pinfunction "1_1") (pintype "passive"))
      (node (ref "C2") (pin "1") (pinfunction "1_1") (pintype "passive"))
      (node (ref "C3") (pin "1") (pinfunction "1_1") (pintype "passive"))
      (node (ref "C6") (pin "1") (pinfunction "1_1") (pintype "passive"))
      (node (ref "C7") (pin "1") (pinfunction "1_1") (pintype "passive"))
      (node (ref "D10") (pin "C") (pinfunction "C_C") (pintype "passive"))
      (node (ref "D3") (pin "C") (pinfunction "C_C") (pintype "passive"))
      (node (ref "D6") (pin "C") (pinfunction "C_C") (pintype "passive"))
      (node (ref "D8") (pin "C") (pinfunction "C_C") (pintype "passive"))
      (node (ref "R1") (pin "1") (pinfunction "1_1") (pintype "passive"))
      (node (ref "R10") (pin "2") (pinfunction "2_2") (pintype "passive"))
      (node (ref "R13") (pin "2") (pinfunction "2_2") (pintype "passive"))
      (node (ref "R14") (pin "2") (pinfunction "2_2") (pintype "passive"))
      (node (ref "R15") (pin "2") (pinfunction "2_2") (pintype "passive"))
      (node (ref "R16") (pin "2") (pinfunction "2_2") (pintype "passive"))
      (node (ref "R17") (pin "2") (pinfunction "2_2") (pintype "passive"))
      (node (ref "R18") (pin "2") (pinfunction "2_2") (pintype "passive"))
      (node (ref "R2") (pin "1") (pinfunction "1_1") (pintype "passive"))
      (node (ref "R21") (pin "2") (pinfunction "2_2") (pintype "passive"))
      (node (ref "R22") (pin "2") (pinfunction "2_2") (pintype "passive"))
      (node (ref "R26") (pin "2") (pinfunction "2_2") (pintype "passive"))
      (node (ref "R27") (pin "1") (pinfunction "1_1") (pintype "passive"))
      (node (ref "R28") (pin "2") (pinfunction "2_2") (pintype "passive"))
      (node (ref "R3") (pin "1") (pinfunction "1_1") (pintype "passive"))
      (node (ref "R4") (pin "1") (pinfunction "1_1") (pintype "passive"))
      (node (ref "R5") (pin "1") (pinfunction "1_1") (pintype "passive"))
      (node (ref "R6") (pin "1") (pinfunction "1_1") (pintype "passive"))
      (node (ref "R7") (pin "2") (pinfunction "2_2") (pintype "passive"))
      (node (ref "R8") (pin "2") (pinfunction "2_2") (pintype "passive"))
      (node (ref "R9") (pin "2") (pinfunction "2_2") (pintype "passive"))
      (node (ref "U$20") (pin "1") (pinfunction "1_1") (pintype "passive"))
      (node (ref "U$51") (pin "RESET") (pinfunction "RESET_RESET") (pintype "bidirectional"))
      (node (ref "U$67") (pin "3V3-1") (pinfunction "3V3-2_3V3-1") (pintype "bidirectional"))
      (node (ref "U1") (pin "2") (pinfunction "CSB_2") (pintype "input"))
      (node (ref "U1") (pin "6") (pinfunction "VDDIO_6") (pintype "power_in"))
      (node (ref "U1") (pin "8") (pinfunction "VDD_8") (pintype "power_in"))
      (node (ref "U2") (pin "2") (pinfunction "CSB_2") (pintype "input"))
      (node (ref "U2") (pin "6") (pinfunction "VDDIO_6") (pintype "power_in"))
      (node (ref "U2") (pin "8") (pinfunction "VDD_8") (pintype "power_in"))
      (node (ref "U3") (pin "2") (pinfunction "CSB_2") (pintype "input"))
      (node (ref "U3") (pin "6") (pinfunction "VDDIO_6") (pintype "power_in"))
      (node (ref "U3") (pin "8") (pinfunction "VDD_8") (pintype "power_in"))
      (node (ref "U4") (pin "2") (pinfunction "CSB_2") (pintype "input"))
      (node (ref "U4") (pin "6") (pinfunction "VDDIO_6") (pintype "power_in"))
      (node (ref "U4") (pin "8") (pinfunction "VDD_8") (pintype "power_in"))
      (node (ref "U5") (pin "2") (pinfunction "CSB_2") (pintype "input"))
      (node (ref "U5") (pin "6") (pinfunction "VDDIO_6") (pintype "power_in"))
      (node (ref "U5") (pin "8") (pinfunction "VDD_8") (pintype "power_in"))
      (node (ref "U6") (pin "24") (pinfunction "VCC_24") (pintype "bidirectional"))
    )
    (net (code "56") (name "5V") (class "Default")
      (node (ref "3V_REGULATOR") (pin "2") (pinfunction "OUT_2") (pintype "passive"))
      (node (ref "3V_REGULATOR") (pin "4") (pinfunction "OUT_4") (pintype "passive"))
      (node (ref "A4") (pin "2") (pinfunction "2_2") (pintype "passive"))
      (node (ref "C1") (pin "1") (pinfunction "+_1") (pintype "passive"))
      (node (ref "C5") (pin "1") (pinfunction "1_1") (pintype "passive"))
      (node (ref "R53") (pin "1") (pinfunction "1_1") (pintype "passive"))
      (node (ref "U$51") (pin "VCC") (pinfunction "VCC_VCC") (pintype "power_in"))
      (node (ref "U$59") (pin "1") (pinfunction "1_1") (pintype "passive"))
    )
    (net (code "57") (name "12V") (class "Default")
      (node (ref "3V_REGULATOR") (pin "3") (pinfunction "IN_3") (pintype "input"))
      (node (ref "C4") (pin "1") (pinfunction "1_1") (pintype "passive"))
      (node (ref "C8") (pin "1") (pinfunction "1_1") (pintype "passive"))
      (node (ref "C9") (pin "1") (pinfunction "1_1") (pintype "passive"))
      (node (ref "J1") (pin "1") (pinfunction "1_1") (pintype "passive"))
      (node (ref "J2") (pin "1") (pinfunction "1_1") (pintype "passive"))
      (node (ref "J4") (pin "1") (pinfunction "1_1") (pintype "passive"))
      (node (ref "J5") (pin "PWR") (pinfunction "PWR_PWR") (pintype "bidirectional"))
      (node (ref "J6") (pin "1") (pinfunction "1_1") (pintype "passive"))
      (node (ref "R12") (pin "2") (pinfunction "2_2") (pintype "passive"))
      (node (ref "R41") (pin "2") (pinfunction "2_2") (pintype "passive"))
      (node (ref "R44") (pin "2") (pinfunction "2_2") (pintype "passive"))
      (node (ref "R47") (pin "2") (pinfunction "2_2") (pintype "passive"))
      (node (ref "R50") (pin "2") (pinfunction "2_2") (pintype "passive"))
      (node (ref "SP2") (pin "1") (pinfunction "1_1") (pintype "passive"))
      (node (ref "U$40") (pin "1") (pinfunction "1_1") (pintype "passive"))
      (node (ref "U7") (pin "8") (pinfunction "P$V+_8") (pintype "bidirectional"))
      (node (ref "U8") (pin "8") (pinfunction "P$V+_8") (pintype "bidirectional"))
    )
    (net (code "58") (name "GND") (class "Default")
      (node (ref "3V_REGULATOR") (pin "1") (pinfunction "GND_1") (pintype "input"))
      (node (ref "C1") (pin "2") (pinfunction "-_2") (pintype "passive"))
      (node (ref "C10") (pin "2") (pinfunction "2_2") (pintype "passive"))
      (node (ref "C11") (pin "2") (pinfunction "2_2") (pintype "passive"))
      (node (ref "C12") (pin "2") (pinfunction "2_2") (pintype "passive"))
      (node (ref "C13") (pin "2") (pinfunction "2_2") (pintype "passive"))
      (node (ref "C14") (pin "2") (pinfunction "2_2") (pintype "passive"))
      (node (ref "C15") (pin "2") (pinfunction "2_2") (pintype "passive"))
      (node (ref "C2") (pin "2") (pinfunction "2_2") (pintype "passive"))
      (node (ref "C3") (pin "2") (pinfunction "2_2") (pintype "passive"))
      (node (ref "C4") (pin "2") (pinfunction "2_2") (pintype "passive"))
      (node (ref "C5") (pin "2") (pinfunction "2_2") (pintype "passive"))
      (node (ref "C6") (pin "2") (pinfunction "2_2") (pintype "passive"))
      (node (ref "C7") (pin "2") (pinfunction "2_2") (pintype "passive"))
      (node (ref "C8") (pin "2") (pinfunction "2_2") (pintype "passive"))
      (node (ref "C9") (pin "2") (pinfunction "2_2") (pintype "passive"))
      (node (ref "D11") (pin "A") (pinfunction "A_A") (pintype "passive"))
      (node (ref "D2") (pin "C") (pinfunction "C_C") (pintype "passive"))
      (node (ref "D5") (pin "A") (pinfunction "A_A") (pintype "passive"))
      (node (ref "D7") (pin "A") (pinfunction "A_A") (pintype "passive"))
      (node (ref "D9") (pin "A") (pinfunction "A_A") (pintype "passive"))
      (node (ref "J1") (pin "2") (pinfunction "2_2") (pintype "passive"))
      (node (ref "J2") (pin "2") (pinfunction "2_2") (pintype "passive"))
      (node (ref "J4") (pin "2") (pinfunction "2_2") (pintype "passive"))
      (node (ref "J5") (pin "GND") (pinfunction "GND_GND") (pintype "bidirectional"))
      (node (ref "J5") (pin "GNDBREAK") (pinfunction "GNDBREAK_GNDBREAK") (pintype "bidirectional"))
      (node (ref "J6") (pin "2") (pinfunction "2_2") (pintype "passive"))
      (node (ref "Q2") (pin "1") (pinfunction "E_1") (pintype "passive"))
      (node (ref "R11") (pin "1") (pinfunction "1_1") (pintype "passive"))
      (node (ref "R19") (pin "2") (pinfunction "2_2") (pintype "passive"))
      (node (ref "R20") (pin "2") (pinfunction "2_2") (pintype "passive"))
      (node (ref "R23") (pin "1") (pinfunction "1_1") (pintype "passive"))
      (node (ref "R25") (pin "2") (pinfunction "2_2") (pintype "passive"))
      (node (ref "R33") (pin "1") (pinfunction "1_1") (pintype "passive"))
      (node (ref "R35") (pin "1") (pinfunction "1_1") (pintype "passive"))
      (node (ref "R37") (pin "1") (pinfunction "1_1") (pintype "passive"))
      (node (ref "R39") (pin "1") (pinfunction "1_1") (pintype "passive"))
      (node (ref "R42") (pin "1") (pinfunction "1_1") (pintype "passive"))
      (node (ref "R45") (pin "1") (pinfunction "1_1") (pintype "passive"))
      (node (ref "R48") (pin "1") (pinfunction "1_1") (pintype "passive"))
      (node (ref "R51") (pin "1") (pinfunction "1_1") (pintype "passive"))
      (node (ref "R54") (pin "1") (pinfunction "1_1") (pintype "passive"))
      (node (ref "R55") (pin "1") (pinfunction "1_1") (pintype "passive"))
      (node (ref "R56") (pin "1") (pinfunction "1_1") (pintype "passive"))
      (node (ref "R57") (pin "1") (pinfunction "1_1") (pintype "passive"))
      (node (ref "R58") (pin "1") (pinfunction "1_1") (pintype "passive"))
      (node (ref "R59") (pin "1") (pinfunction "1_1") (pintype "passive"))
      (node (ref "S3") (pin "3") (pinfunction "2_3") (pintype "passive"))
      (node (ref "S5") (pin "C") (pinfunction "C_C") (pintype "bidirectional"))
      (node (ref "S5") (pin "SW-") (pinfunction "SW-_SW-") (pintype "bidirectional"))
      (node (ref "U$31") (pin "1") (pinfunction "1_1") (pintype "passive"))
      (node (ref "U$51") (pin "GND") (pinfunction "GND_GND") (pintype "power_in"))
      (node (ref "U$63") (pin "1") (pinfunction "1_1") (pintype "passive"))
      (node (ref "U$64") (pin "1") (pinfunction "1_1") (pintype "passive"))
      (node (ref "U$65") (pin "1") (pinfunction "1_1") (pintype "passive"))
      (node (ref "U$66") (pin "1") (pinfunction "1_1") (pintype "passive"))
      (node (ref "U$67") (pin "GND1") (pinfunction "GND3_GND1") (pintype "bidirectional"))
      (node (ref "U$67") (pin "GND3") (pinfunction "GND4_GND3") (pintype "bidirectional"))
      (node (ref "U1") (pin "1") (pinfunction "GND_1") (pintype "power_in"))
      (node (ref "U1") (pin "7") (pinfunction "GND_7") (pintype "power_in"))
      (node (ref "U2") (pin "1") (pinfunction "GND_1") (pintype "power_in"))
      (node (ref "U2") (pin "7") (pinfunction "GND_7") (pintype "power_in"))
      (node (ref "U3") (pin "1") (pinfunction "GND_1") (pintype "power_in"))
      (node (ref "U3") (pin "7") (pinfunction "GND_7") (pintype "power_in"))
      (node (ref "U4") (pin "1") (pinfunction "GND_1") (pintype "power_in"))
      (node (ref "U4") (pin "7") (pinfunction "GND_7") (pintype "power_in"))
      (node (ref "U5") (pin "1") (pinfunction "GND_1") (pintype "power_in"))
      (node (ref "U5") (pin "7") (pinfunction "GND_7") (pintype "power_in"))
      (node (ref "U6") (pin "12") (pinfunction "GND_12") (pintype "bidirectional"))
      (node (ref "U7") (pin "4") (pinfunction "P$V-_4") (pintype "bidirectional"))
      (node (ref "U8") (pin "4") (pinfunction "P$V-_4") (pintype "bidirectional"))
    )
    (net (code "59") (name "Net-(C11-Pad1)") (class "Default")
      (node (ref "C11") (pin "1") (pinfunction "1_1") (pintype "passive"))
      (node (ref "R41") (pin "1") (pinfunction "1_1") (pintype "passive"))
      (node (ref "R42") (pin "2") (pinfunction "2_2") (pintype "passive"))
      (node (ref "R43") (pin "1") (pinfunction "1_1") (pintype "passive"))
    )
    (net (code "60") (name "Net-(C13-Pad1)") (class "Default")
      (node (ref "C13") (pin "1") (pinfunction "1_1") (pintype "passive"))
      (node (ref "R44") (pin "1") (pinfunction "1_1") (pintype "passive"))
      (node (ref "R45") (pin "2") (pinfunction "2_2") (pintype "passive"))
      (node (ref "R46") (pin "1") (pinfunction "1_1") (pintype "passive"))
    )
    (net (code "61") (name "Net-(C14-Pad1)") (class "Default")
      (node (ref "C14") (pin "1") (pinfunction "1_1") (pintype "passive"))
      (node (ref "R47") (pin "1") (pinfunction "1_1") (pintype "passive"))
      (node (ref "R48") (pin "2") (pinfunction "2_2") (pintype "passive"))
      (node (ref "R49") (pin "1") (pinfunction "1_1") (pintype "passive"))
    )
    (net (code "62") (name "Net-(C15-Pad1)") (class "Default")
      (node (ref "C15") (pin "1") (pinfunction "1_1") (pintype "passive"))
      (node (ref "R50") (pin "1") (pinfunction "1_1") (pintype "passive"))
      (node (ref "R51") (pin "2") (pinfunction "2_2") (pintype "passive"))
      (node (ref "R52") (pin "1") (pinfunction "1_1") (pintype "passive"))
    )
    (net (code "63") (name "Net-(D2-PadA)") (class "Default")
      (node (ref "D2") (pin "A") (pinfunction "A_A") (pintype "passive"))
      (node (ref "R12") (pin "1") (pinfunction "1_1") (pintype "passive"))
    )
    (net (code "64") (name "Net-(D12-C)") (class "Default")
      (node (ref "D12") (pin "K") (pinfunction "C_K") (pintype "passive"))
      (node (ref "R11") (pin "2") (pinfunction "2_2") (pintype "passive"))
    )
    (net (code "65") (name "Net-(D13-C)") (class "Default")
      (node (ref "D13") (pin "K") (pinfunction "C_K") (pintype "passive"))
      (node (ref "R23") (pin "2") (pinfunction "2_2") (pintype "passive"))
    )
    (net (code "66") (name "Net-(D14-C)") (class "Default")
      (node (ref "D14") (pin "K") (pinfunction "C_K") (pintype "passive"))
      (node (ref "R54") (pin "2") (pinfunction "2_2") (pintype "passive"))
    )
    (net (code "67") (name "Net-(D15-C)") (class "Default")
      (node (ref "D15") (pin "K") (pinfunction "C_K") (pintype "passive"))
      (node (ref "R55") (pin "2") (pinfunction "2_2") (pintype "passive"))
    )
    (net (code "68") (name "Net-(D16-C)") (class "Default")
      (node (ref "D16") (pin "K") (pinfunction "C_K") (pintype "passive"))
      (node (ref "R56") (pin "2") (pinfunction "2_2") (pintype "passive"))
    )
    (net (code "69") (name "Net-(D17-C)") (class "Default")
      (node (ref "D17") (pin "K") (pinfunction "C_K") (pintype "passive"))
      (node (ref "R57") (pin "2") (pinfunction "2_2") (pintype "passive"))
    )
    (net (code "70") (name "Net-(D18-C)") (class "Default")
      (node (ref "D18") (pin "K") (pinfunction "C_K") (pintype "passive"))
      (node (ref "R58") (pin "2") (pinfunction "2_2") (pintype "passive"))
    )
    (net (code "71") (name "Net-(D19-C)") (class "Default")
      (node (ref "D19") (pin "K") (pinfunction "C_K") (pintype "passive"))
      (node (ref "R59") (pin "2") (pinfunction "2_2") (pintype "passive"))
    )
    (net (code "72") (name "Net-(Q2-B)") (class "Default")
      (node (ref "Q2") (pin "2") (pinfunction "B_2") (pintype "passive"))
      (node (ref "R24") (pin "1") (pinfunction "1_1") (pintype "passive"))
    )
    (net (code "73") (name "Net-(Q2-C)") (class "Default")
      (node (ref "Q2") (pin "3") (pinfunction "C_3") (pintype "passive"))
      (node (ref "SP2") (pin "2") (pinfunction "2_2") (pintype "passive"))
    )
    (net (code "74") (name "Net-(R53-Pad2)") (class "Default")
      (node (ref "R53") (pin "2") (pinfunction "2_2") (pintype "passive"))
      (node (ref "U$51") (pin "LED") (pinfunction "LED_LED") (pintype "bidirectional"))
    )
    (net (code "75") (name "Net-(U$67-VIN1)") (class "Default")
      (node (ref "A4") (pin "1") (pinfunction "1_1") (pintype "passive"))
      (node (ref "U$67") (pin "VIN") (pinfunction "VIN1_VIN") (pintype "bidirectional"))
    )
    (net (code "76") (name "Net-(U1-SDO)") (class "Default")
      (node (ref "R3") (pin "2") (pinfunction "2_2") (pintype "passive"))
      (node (ref "U1") (pin "5") (pinfunction "SDO_5") (pintype "output"))
    )
    (net (code "77") (name "Net-(U2-SDO)") (class "Default")
      (node (ref "R2") (pin "2") (pinfunction "2_2") (pintype "passive"))
      (node (ref "U2") (pin "5") (pinfunction "SDO_5") (pintype "output"))
    )
    (net (code "78") (name "Net-(U3-SDO)") (class "Default")
      (node (ref "R4") (pin "2") (pinfunction "2_2") (pintype "passive"))
      (node (ref "U3") (pin "5") (pinfunction "SDO_5") (pintype "output"))
    )
    (net (code "79") (name "Net-(U4-SDO)") (class "Default")
      (node (ref "R1") (pin "2") (pinfunction "2_2") (pintype "passive"))
      (node (ref "U4") (pin "5") (pinfunction "SDO_5") (pintype "output"))
    )
    (net (code "80") (name "Net-(U5-SDO)") (class "Default")
      (node (ref "R5") (pin "2") (pinfunction "2_2") (pintype "passive"))
      (node (ref "U5") (pin "5") (pinfunction "SDO_5") (pintype "output"))
    )
    (net (code "81") (name "Net-(U7A--IN)") (class "Default")
      (node (ref "R29") (pin "1") (pinfunction "1_1") (pintype "passive"))
      (node (ref "R43") (pin "2") (pinfunction "2_2") (pintype "passive"))
      (node (ref "U7") (pin "2") (pinfunction "-IN_2") (pintype "input"))
    )
    (net (code "82") (name "Net-(U7A-OUT)") (class "Default")
      (node (ref "R29") (pin "2") (pinfunction "2_2") (pintype "passive"))
      (node (ref "R40") (pin "2") (pinfunction "2_2") (pintype "passive"))
      (node (ref "U7") (pin "1") (pinfunction "OUT_1") (pintype "output"))
    )
    (net (code "83") (name "Net-(U7B--IN)") (class "Default")
      (node (ref "R30") (pin "1") (pinfunction "1_1") (pintype "passive"))
      (node (ref "R46") (pin "2") (pinfunction "2_2") (pintype "passive"))
      (node (ref "U7") (pin "6") (pinfunction "-IN_6") (pintype "input"))
    )
    (net (code "84") (name "Net-(U7B-OUT)") (class "Default")
      (node (ref "R30") (pin "2") (pinfunction "2_2") (pintype "passive"))
      (node (ref "R34") (pin "2") (pinfunction "2_2") (pintype "passive"))
      (node (ref "U7") (pin "7") (pinfunction "OUT_7") (pintype "output"))
    )
    (net (code "85") (name "Net-(U8A--IN)") (class "Default")
      (node (ref "R31") (pin "1") (pinfunction "1_1") (pintype "passive"))
      (node (ref "R49") (pin "2") (pinfunction "2_2") (pintype "passive"))
      (node (ref "U8") (pin "2") (pinfunction "-IN_2") (pintype "input"))
    )
    (net (code "86") (name "Net-(U8A-OUT)") (class "Default")
      (node (ref "R31") (pin "2") (pinfunction "2_2") (pintype "passive"))
      (node (ref "R36") (pin "2") (pinfunction "2_2") (pintype "passive"))
      (node (ref "U8") (pin "1") (pinfunction "OUT_1") (pintype "output"))
    )
    (net (code "87") (name "Net-(U8B--IN)") (class "Default")
      (node (ref "R32") (pin "1") (pinfunction "1_1") (pintype "passive"))
      (node (ref "R52") (pin "2") (pinfunction "2_2") (pintype "passive"))
      (node (ref "U8") (pin "6") (pinfunction "-IN_6") (pintype "input"))
    )
    (net (code "88") (name "Net-(U8B-OUT)") (class "Default")
      (node (ref "R32") (pin "2") (pinfunction "2_2") (pintype "passive"))
      (node (ref "R38") (pin "2") (pinfunction "2_2") (pintype "passive"))
      (node (ref "U8") (pin "7") (pinfunction "OUT_7") (pintype "output"))
    )
    (net (code "89") (name "unconnected-(U$15-Pad1)") (class "Default")
      (node (ref "U$15") (pin "1") (pinfunction "1_1") (pintype "passive"))
    )
    (net (code "90") (name "unconnected-(U$45-Pad1)") (class "Default")
      (node (ref "U$45") (pin "1") (pinfunction "1_1") (pintype "passive"))
    )
    (net (code "91") (name "unconnected-(U$58-Pad1)") (class "Default")
      (node (ref "U$58") (pin "1") (pinfunction "1_1") (pintype "passive"))
    )
    (net (code "92") (name "unconnected-(U$60-Pad1)") (class "Default")
      (node (ref "U$60") (pin "1") (pinfunction "1_1") (pintype "passive"))
    )
    (net (code "93") (name "unconnected-(U$61-Pad1)") (class "Default")
      (node (ref "U$61") (pin "1") (pinfunction "1_1") (pintype "passive"))
    )
    (net (code "94") (name "unconnected-(U$62-Pad1)") (class "Default")
      (node (ref "U$62") (pin "1") (pinfunction "1_1") (pintype "passive"))
    )
    (net (code "95") (name "unconnected-(U$67-25-A11{slash}RX6{slash}SDA2-Pad25-A11{slash}SDA2)") (class "Default")
      (node (ref "U$67") (pin "25-A11/SDA2") (pinfunction "25-A11/RX6/SDA2_25-A11/SDA2") (pintype "bidirectional"))
    )
    (net (code "96") (name "unconnected-(U$67-32-OUT1B-Pad32-OUTB1)") (class "Default")
      (node (ref "U$67") (pin "32-OUTB1") (pinfunction "32-OUT1B_32-OUTB1") (pintype "bidirectional"))
    )
    (net (code "97") (name "unconnected-(U$67-Pad24-A10{slash}TX6{slash}SCL2)") (class "Default")
      (node (ref "U$67") (pin "24-A10/TX6/SCL2") (pinfunction "24-A10/TX6/SCL2_24-A10/TX6/SCL2") (pintype "bidirectional"))
    )
    (net (code "98") (name "unconnected-(U$67-Pad26-A12{slash}MOSI1)") (class "Default")
      (node (ref "U$67") (pin "26-A12/MOSI1") (pinfunction "26-A12/MOSI1_26-A12/MOSI1") (pintype "bidirectional"))
    )
    (net (code "99") (name "unconnected-(U$67-Pad27-A13{slash}SCK1)") (class "Default")
      (node (ref "U$67") (pin "27-A13/SCK1") (pinfunction "27-A13/SCK1_27-A13/SCK1") (pintype "bidirectional"))
    )
    (net (code "100") (name "unconnected-(U$67-Pad30-CRX3)") (class "Default")
      (node (ref "U$67") (pin "30-CRX3") (pinfunction "30-CRX3_30-CRX3") (pintype "bidirectional"))
    )
    (net (code "101") (name "unconnected-(U$67-Pad31-CTX3)") (class "Default")
      (node (ref "U$67") (pin "31-CTX3") (pinfunction "31-CTX3_31-CTX3") (pintype "bidirectional"))
    )
    (net (code "102") (name "unconnected-(U$67-Pad33-MCLK2)") (class "Default")
      (node (ref "U$67") (pin "33-MCLK2") (pinfunction "33-MCLK2_33-MCLK2") (pintype "bidirectional"))
    )
  )
)
